# NRF51822.net
KiCad netlist of a schematic drawn in Altium Designer
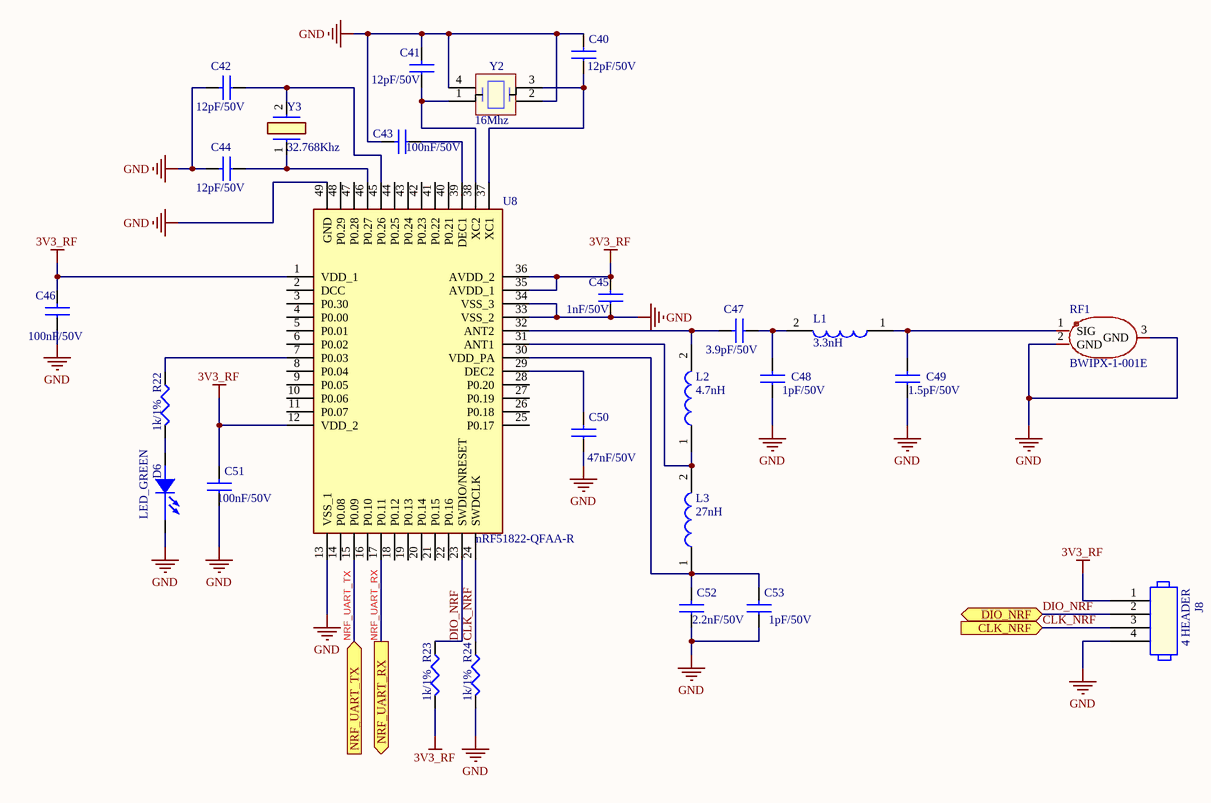
[diagram p0: NRF51822.SchDoc]

(export (version "E")
  (design (tool "Eeschema 10.0.6"))
  (components
    (comp (ref "C40") (value "12pF/50V") (footprint "C0402") (libsource (lib "*") (part "CAP NP")))
    (comp (ref "C41") (value "12pF/50V") (footprint "C0402") (libsource (lib "*") (part "CAP NP")))
    (comp (ref "C42") (value "12pF/50V") (footprint "C0402") (libsource (lib "*") (part "CAP NP")))
    (comp (ref "C43") (value "100nF/50V") (footprint "C0402") (libsource (lib "*") (part "CAP NP")))
    (comp (ref "C44") (value "12pF/50V") (footprint "C0402") (libsource (lib "*") (part "CAP NP")))
    (comp (ref "C45") (value "1nF/50V") (footprint "C0402") (libsource (lib "*") (part "CAP NP")))
    (comp (ref "C46") (value "100nF/50V") (footprint "C0402") (libsource (lib "*") (part "CAP NP")))
    (comp (ref "C47") (value "3.9pF/50V") (footprint "C0402") (libsource (lib "*") (part "CAP NP")))
    (comp (ref "C48") (value "1pF/50V") (footprint "C0402") (libsource (lib "*") (part "CAP NP")))
    (comp (ref "C49") (value "1.5pF/50V") (footprint "C0402") (libsource (lib "*") (part "CAP NP")))
    (comp (ref "C50") (value "47nF/50V") (footprint "C0402") (libsource (lib "*") (part "CAP NP")))
    (comp (ref "C51") (value "100nF/50V") (footprint "C0402") (libsource (lib "*") (part "CAP NP")))
    (comp (ref "C52") (value "2.2nF/50V") (footprint "C0402") (libsource (lib "*") (part "CAP NP")))
    (comp (ref "C53") (value "1pF/50V") (footprint "C0402") (libsource (lib "*") (part "CAP NP")))
    (comp (ref "D6") (value "LED_GREEN") (footprint "LED0603") (libsource (lib "*") (part "LED")))
    (comp (ref "J8") (value "4 HEADER") (footprint "ISP-4P-2_54") (libsource (lib "*") (part "4 HEADER")))
    (comp (ref "L1")
      (value "3.3nH")
      (footprint "LQG15WH0N7B02D")
      (description "Inductor")
      (fields
        (field (name "MANUFACTURER_PART_NUMBER") "LQG15HS4N7C02D")
        (field (name "MOUSER PART NUMBER") "81-LQG15HS4N7C02D")
      )
      (libsource (lib "VESC_DEVICE_Library") (part "LQG15HS4N7C02D"))
    )
    (comp (ref "L2")
      (value "4.7nH")
      (footprint "LQG15WH0N7B02D")
      (description "Inductor")
      (fields
        (field (name "MANUFACTURER_PART_NUMBER") "LQG15HS4N7C02D")
        (field (name "MOUSER PART NUMBER") "81-LQG15HS4N7C02D")
      )
      (libsource (lib "VESC_DEVICE_Library") (part "LQG15HS4N7C02D"))
    )
    (comp (ref "L3")
      (value "27nH")
      (footprint "LQG15WH0N7B02D")
      (description "Inductor")
      (fields
        (field (name "MANUFACTURER_PART_NUMBER") "LQG15HS4N7C02D")
        (field (name "MOUSER PART NUMBER") "81-LQG15HS4N7C02D")
      )
      (libsource (lib "VESC_DEVICE_Library") (part "LQG15HS4N7C02D"))
    )
    (comp (ref "R22") (value "1k/1%") (footprint "R0402") (libsource (lib "*") (part "RESISTOR")))
    (comp (ref "R23") (value "1k/1%") (footprint "R0402") (libsource (lib "*") (part "RESISTOR")))
    (comp (ref "R24") (value "1k/1%") (footprint "R0402") (libsource (lib "*") (part "RESISTOR")))
    (comp (ref "RF1")
      (value "BWIPX-1-001E")
      (footprint "IPEX-SMD_BWIPX-1-001E")
      (fields (field (name "MANUFACTURER") "BAT WIRELESS(蝙蝠无线)"))
      (libsource (lib "VESC_DEVICE_Library") (part "BWIPX-1-001E"))
    )
    (comp (ref "U8")
      (value "nRF51822-QFAA-R")
      (footprint "QFN40P600X600X95-49N-D")
      (description "Integrated Circuit")
      (fields
        (field (name "MOUSER PART NUMBER") "949-NRF51822-QFAA-R")
        (field (name "ARROW PART NUMBER") "NRF51822-QFAA-R")
      )
      (libsource (lib "VESC_DEVICE_Library") (part "nRF51822-QFAA-R"))
    )
    (comp (ref "Y2")
      (value "16Mhz")
      (footprint "Q22FA12800400")
      (description "Crystal or Oscillator")
      (fields (field (name "MANUFACTURER_PART_NUMBER") "Q22FA12800400"))
      (libsource (lib "VESC_DEVICE_Library") (part "Q22FA12800400"))
    )
    (comp (ref "Y3")
      (value "32.768Khz")
      (footprint "ABS0532768KHZ9T")
      (description "Crystal or Oscillator")
      (fields
        (field (name "MANUFACTURER_PART_NUMBER") "ABS05-32.768KHZ-9-T")
        (field (name "MOUSER PART NUMBER") "815-ABS05-32.768K9T")
      )
      (libsource (lib "VESC_DEVICE_Library") (part "ABS05-32.768KHZ-9-T"))
    )
  )
  (nets
    (net (code "1") (name "/CLK_NRF") (class "Default")
      (node (ref "J8") (pin "3") (pinfunction "3_3") (pintype "passive"))
      (node (ref "R24") (pin "2") (pinfunction "2_2") (pintype "passive"))
      (node (ref "U8") (pin "24") (pinfunction "SWDCLK_24") (pintype "passive"))
    )
    (net (code "2") (name "/DIO_NRF") (class "Default")
      (node (ref "J8") (pin "2") (pinfunction "2_2") (pintype "passive"))
      (node (ref "R23") (pin "2") (pinfunction "2_2") (pintype "passive"))
      (node (ref "U8") (pin "23") (pinfunction "SWDIO/NRESET_23") (pintype "passive"))
    )
    (net (code "3") (name "/NRF_UART_RX") (class "Default")
      (node (ref "U8") (pin "17") (pinfunction "P0.11_17") (pintype "passive"))
    )
    (net (code "4") (name "/NRF_UART_TX") (class "Default")
      (node (ref "U8") (pin "15") (pinfunction "P0.09_15") (pintype "passive"))
    )
    (net (code "5") (name "3V3_RF") (class "Default")
      (node (ref "C45") (pin "2") (pinfunction "2_2") (pintype "passive"))
      (node (ref "C46") (pin "2") (pinfunction "2_2") (pintype "passive"))
      (node (ref "C51") (pin "2") (pinfunction "2_2") (pintype "passive"))
      (node (ref "J8") (pin "1") (pinfunction "1_1") (pintype "passive"))
      (node (ref "R23") (pin "1") (pinfunction "1_1") (pintype "passive"))
      (node (ref "U8") (pin "1") (pinfunction "VDD_1_1") (pintype "passive"))
      (node (ref "U8") (pin "12") (pinfunction "VDD_2_12") (pintype "passive"))
      (node (ref "U8") (pin "35") (pinfunction "AVDD_1_35") (pintype "passive"))
      (node (ref "U8") (pin "36") (pinfunction "AVDD_2_36") (pintype "passive"))
    )
    (net (code "6") (name "GND") (class "Default")
      (node (ref "C40") (pin "2") (pinfunction "2_2") (pintype "passive"))
      (node (ref "C41") (pin "2") (pinfunction "2_2") (pintype "passive"))
      (node (ref "C42") (pin "2") (pinfunction "2_2") (pintype "passive"))
      (node (ref "C43") (pin "2") (pinfunction "2_2") (pintype "passive"))
      (node (ref "C44") (pin "2") (pinfunction "2_2") (pintype "passive"))
      (node (ref "C45") (pin "1") (pinfunction "1_1") (pintype "passive"))
      (node (ref "C46") (pin "1") (pinfunction "1_1") (pintype "passive"))
      (node (ref "C48") (pin "1") (pinfunction "1_1") (pintype "passive"))
      (node (ref "C49") (pin "1") (pinfunction "1_1") (pintype "passive"))
      (node (ref "C50") (pin "1") (pinfunction "1_1") (pintype "passive"))
      (node (ref "C51") (pin "1") (pinfunction "1_1") (pintype "passive"))
      (node (ref "C52") (pin "1") (pinfunction "1_1") (pintype "passive"))
      (node (ref "C53") (pin "1") (pinfunction "1_1") (pintype "passive"))
      (node (ref "D6") (pin "1") (pinfunction "CATHODE_1") (pintype "passive"))
      (node (ref "J8") (pin "4") (pinfunction "4_4") (pintype "passive"))
      (node (ref "R24") (pin "1") (pinfunction "1_1") (pintype "passive"))
      (node (ref "RF1") (pin "2") (pinfunction "GND_2") (pintype "passive"))
      (node (ref "RF1") (pin "3") (pinfunction "GND_3") (pintype "passive"))
      (node (ref "U8") (pin "13") (pinfunction "VSS_1_13") (pintype "passive"))
      (node (ref "U8") (pin "33") (pinfunction "VSS_2_33") (pintype "passive"))
      (node (ref "U8") (pin "34") (pinfunction "VSS_3_34") (pintype "passive"))
      (node (ref "U8") (pin "49") (pinfunction "GND_49") (pintype "passive"))
      (node (ref "Y2") (pin "2") (pinfunction "GND_1_2") (pintype "passive"))
      (node (ref "Y2") (pin "4") (pinfunction "GND_2_4") (pintype "passive"))
    )
    (net (code "7") (name "Net-(C47-Pad1)") (class "Default")
      (node (ref "C47") (pin "1") (pinfunction "1_1") (pintype "passive"))
      (node (ref "C48") (pin "2") (pinfunction "2_2") (pintype "passive"))
      (node (ref "L1") (pin "2") (pinfunction "2_2") (pintype "passive"))
    )
    (net (code "8") (name "Net-(D6-ANODE)") (class "Default")
      (node (ref "D6") (pin "2") (pinfunction "ANODE_2") (pintype "passive"))
      (node (ref "R22") (pin "1") (pinfunction "1_1") (pintype "passive"))
    )
    (net (code "9") (name "Net-(RF1-SIG)") (class "Default")
      (node (ref "C49") (pin "2") (pinfunction "2_2") (pintype "passive"))
      (node (ref "L1") (pin "1") (pinfunction "1_1") (pintype "passive"))
      (node (ref "RF1") (pin "1") (pinfunction "SIG_1") (pintype "passive"))
    )
    (net (code "10") (name "Net-(U8-ANT1)") (class "Default")
      (node (ref "L2") (pin "1") (pinfunction "1_1") (pintype "passive"))
      (node (ref "L3") (pin "2") (pinfunction "2_2") (pintype "passive"))
      (node (ref "U8") (pin "31") (pinfunction "ANT1_31") (pintype "passive"))
    )
    (net (code "11") (name "Net-(U8-ANT2)") (class "Default")
      (node (ref "C47") (pin "2") (pinfunction "2_2") (pintype "passive"))
      (node (ref "L2") (pin "2") (pinfunction "2_2") (pintype "passive"))
      (node (ref "U8") (pin "32") (pinfunction "ANT2_32") (pintype "passive"))
    )
    (net (code "12") (name "Net-(U8-DEC1)") (class "Default")
      (node (ref "C43") (pin "1") (pinfunction "1_1") (pintype "passive"))
      (node (ref "U8") (pin "39") (pinfunction "DEC1_39") (pintype "passive"))
    )
    (net (code "13") (name "Net-(U8-DEC2)") (class "Default")
      (node (ref "C50") (pin "2") (pinfunction "2_2") (pintype "passive"))
      (node (ref "U8") (pin "29") (pinfunction "DEC2_29") (pintype "passive"))
    )
    (net (code "14") (name "Net-(U8-P0.03)") (class "Default")
      (node (ref "R22") (pin "2") (pinfunction "2_2") (pintype "passive"))
      (node (ref "U8") (pin "7") (pinfunction "P0.03_7") (pintype "passive"))
    )
    (net (code "15") (name "Net-(U8-P0.26)") (class "Default")
      (node (ref "C42") (pin "1") (pinfunction "1_1") (pintype "passive"))
      (node (ref "U8") (pin "45") (pinfunction "P0.26_45") (pintype "passive"))
      (node (ref "Y3") (pin "2") (pinfunction "2_2") (pintype "passive"))
    )
    (net (code "16") (name "Net-(U8-P0.27)") (class "Default")
      (node (ref "C44") (pin "1") (pinfunction "1_1") (pintype "passive"))
      (node (ref "U8") (pin "46") (pinfunction "P0.27_46") (pintype "passive"))
      (node (ref "Y3") (pin "1") (pinfunction "1_1") (pintype "passive"))
    )
    (net (code "17") (name "Net-(U8-VDD_PA)") (class "Default")
      (node (ref "C52") (pin "2") (pinfunction "2_2") (pintype "passive"))
      (node (ref "C53") (pin "2") (pinfunction "2_2") (pintype "passive"))
      (node (ref "L3") (pin "1") (pinfunction "1_1") (pintype "passive"))
      (node (ref "U8") (pin "30") (pinfunction "VDD_PA_30") (pintype "passive"))
    )
    (net (code "18") (name "Net-(U8-XC1)") (class "Default")
      (node (ref "C40") (pin "1") (pinfunction "1_1") (pintype "passive"))
      (node (ref "U8") (pin "37") (pinfunction "XC1_37") (pintype "passive"))
      (node (ref "Y2") (pin "3") (pinfunction "CRYSTAL_2_3") (pintype "passive"))
    )
    (net (code "19") (name "Net-(U8-XC2)") (class "Default")
      (node (ref "C41") (pin "1") (pinfunction "1_1") (pintype "passive"))
      (node (ref "U8") (pin "38") (pinfunction "XC2_38") (pintype "passive"))
      (node (ref "Y2") (pin "1") (pinfunction "CRYSTAL_1_1") (pintype "passive"))
    )
    (net (code "20") (name "unconnected-(U8-DCC-Pad2)") (class "Default")
      (node (ref "U8") (pin "2") (pinfunction "DCC_2") (pintype "passive"))
    )
    (net (code "21") (name "unconnected-(U8-P0.00-Pad4)") (class "Default")
      (node (ref "U8") (pin "4") (pinfunction "P0.00_4") (pintype "passive"))
    )
    (net (code "22") (name "unconnected-(U8-P0.01-Pad5)") (class "Default")
      (node (ref "U8") (pin "5") (pinfunction "P0.01_5") (pintype "passive"))
    )
    (net (code "23") (name "unconnected-(U8-P0.02-Pad6)") (class "Default")
      (node (ref "U8") (pin "6") (pinfunction "P0.02_6") (pintype "passive"))
    )
    (net (code "24") (name "unconnected-(U8-P0.04-Pad8)") (class "Default")
      (node (ref "U8") (pin "8") (pinfunction "P0.04_8") (pintype "passive"))
    )
    (net (code "25") (name "unconnected-(U8-P0.05-Pad9)") (class "Default")
      (node (ref "U8") (pin "9") (pinfunction "P0.05_9") (pintype "passive"))
    )
    (net (code "26") (name "unconnected-(U8-P0.06-Pad10)") (class "Default")
      (node (ref "U8") (pin "10") (pinfunction "P0.06_10") (pintype "passive"))
    )
    (net (code "27") (name "unconnected-(U8-P0.07-Pad11)") (class "Default")
      (node (ref "U8") (pin "11") (pinfunction "P0.07_11") (pintype "passive"))
    )
    (net (code "28") (name "unconnected-(U8-P0.08-Pad14)") (class "Default")
      (node (ref "U8") (pin "14") (pinfunction "P0.08_14") (pintype "passive"))
    )
    (net (code "29") (name "unconnected-(U8-P0.10-Pad16)") (class "Default")
      (node (ref "U8") (pin "16") (pinfunction "P0.10_16") (pintype "passive"))
    )
    (net (code "30") (name "unconnected-(U8-P0.12-Pad18)") (class "Default")
      (node (ref "U8") (pin "18") (pinfunction "P0.12_18") (pintype "passive"))
    )
    (net (code "31") (name "unconnected-(U8-P0.13-Pad19)") (class "Default")
      (node (ref "U8") (pin "19") (pinfunction "P0.13_19") (pintype "passive"))
    )
    (net (code "32") (name "unconnected-(U8-P0.14-Pad20)") (class "Default")
      (node (ref "U8") (pin "20") (pinfunction "P0.14_20") (pintype "passive"))
    )
    (net (code "33") (name "unconnected-(U8-P0.15-Pad21)") (class "Default")
      (node (ref "U8") (pin "21") (pinfunction "P0.15_21") (pintype "passive"))
    )
    (net (code "34") (name "unconnected-(U8-P0.16-Pad22)") (class "Default")
      (node (ref "U8") (pin "22") (pinfunction "P0.16_22") (pintype "passive"))
    )
    (net (code "35") (name "unconnected-(U8-P0.17-Pad25)") (class "Default")
      (node (ref "U8") (pin "25") (pinfunction "P0.17_25") (pintype "passive"))
    )
    (net (code "36") (name "unconnected-(U8-P0.18-Pad26)") (class "Default")
      (node (ref "U8") (pin "26") (pinfunction "P0.18_26") (pintype "passive"))
    )
    (net (code "37") (name "unconnected-(U8-P0.19-Pad27)") (class "Default")
      (node (ref "U8") (pin "27") (pinfunction "P0.19_27") (pintype "passive"))
    )
    (net (code "38") (name "unconnected-(U8-P0.20-Pad28)") (class "Default")
      (node (ref "U8") (pin "28") (pinfunction "P0.20_28") (pintype "passive"))
    )
    (net (code "39") (name "unconnected-(U8-P0.21-Pad40)") (class "Default")
      (node (ref "U8") (pin "40") (pinfunction "P0.21_40") (pintype "passive"))
    )
    (net (code "40") (name "unconnected-(U8-P0.22-Pad41)") (class "Default")
      (node (ref "U8") (pin "41") (pinfunction "P0.22_41") (pintype "passive"))
    )
    (net (code "41") (name "unconnected-(U8-P0.23-Pad42)") (class "Default")
      (node (ref "U8") (pin "42") (pinfunction "P0.23_42") (pintype "passive"))
    )
    (net (code "42") (name "unconnected-(U8-P0.24-Pad43)") (class "Default")
      (node (ref "U8") (pin "43") (pinfunction "P0.24_43") (pintype "passive"))
    )
    (net (code "43") (name "unconnected-(U8-P0.25-Pad44)") (class "Default")
      (node (ref "U8") (pin "44") (pinfunction "P0.25_44") (pintype "passive"))
    )
    (net (code "44") (name "unconnected-(U8-P0.28-Pad47)") (class "Default")
      (node (ref "U8") (pin "47") (pinfunction "P0.28_47") (pintype "passive"))
    )
    (net (code "45") (name "unconnected-(U8-P0.29-Pad48)") (class "Default")
      (node (ref "U8") (pin "48") (pinfunction "P0.29_48") (pintype "passive"))
    )
    (net (code "46") (name "unconnected-(U8-P0.30-Pad3)") (class "Default")
      (node (ref "U8") (pin "3") (pinfunction "P0.30_3") (pintype "passive"))
    )
  )
)
